# PLC_Relay.net
KiCad netlist of a schematic drawn in Altium Designer
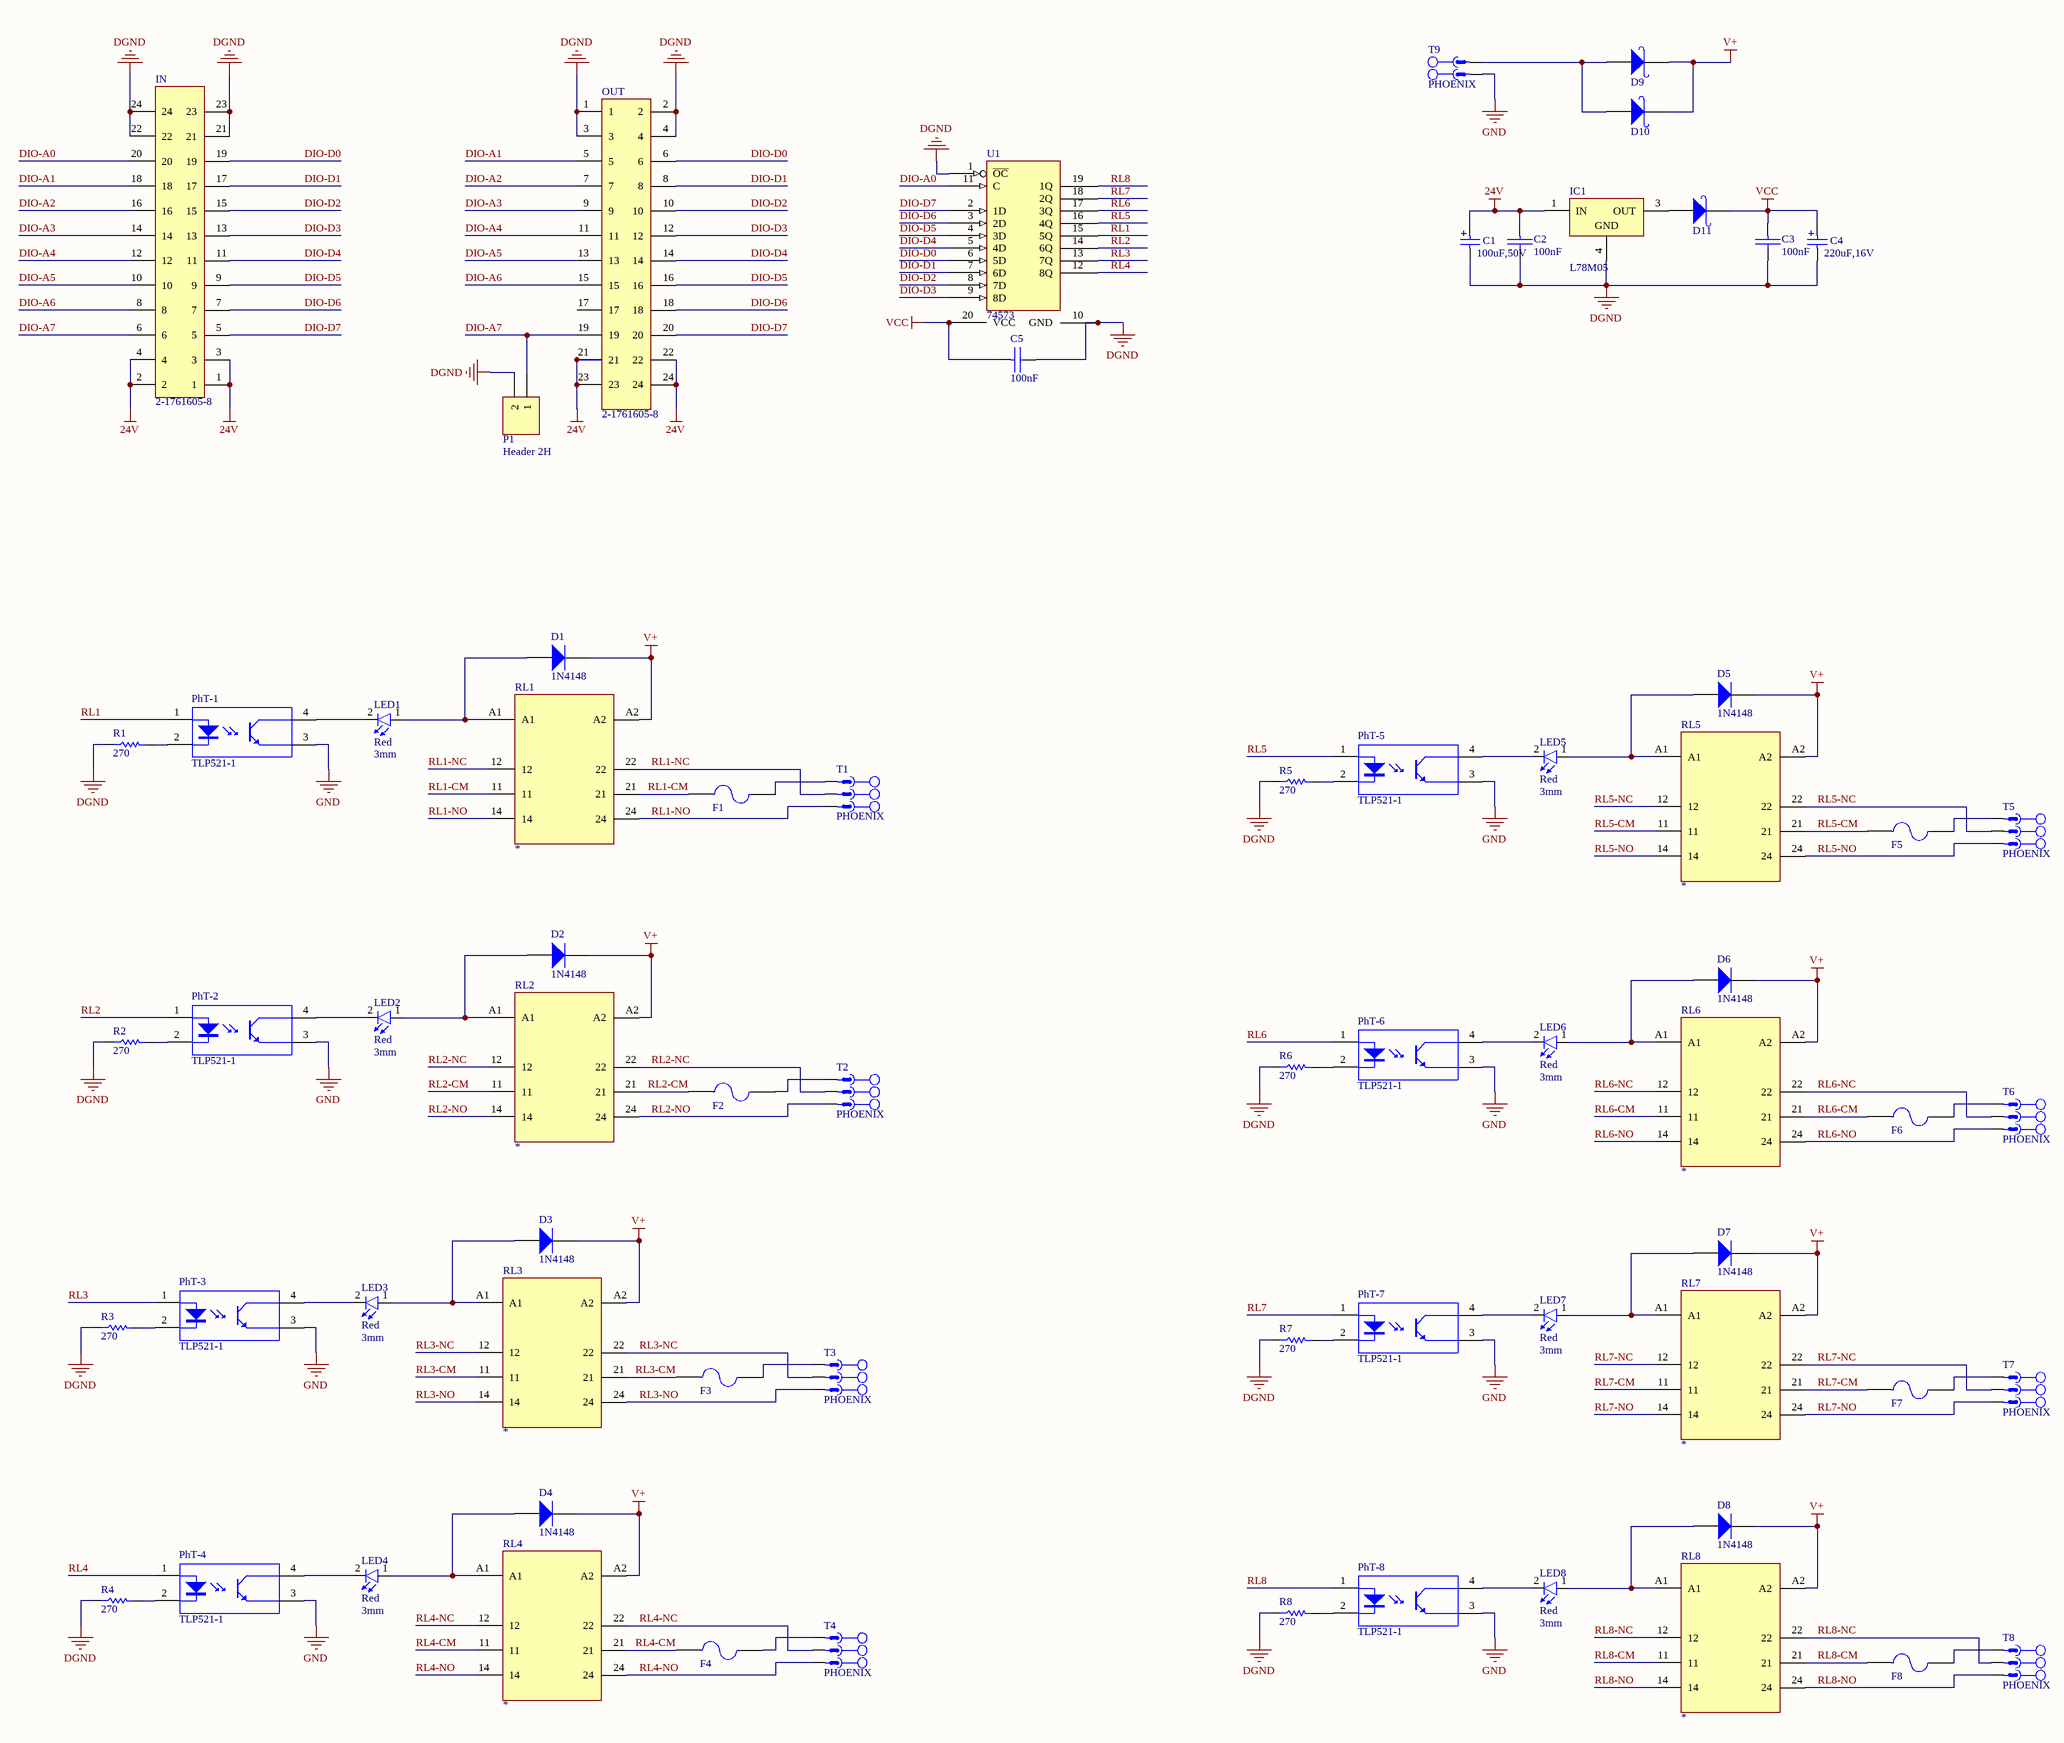
[diagram p0: PLC_Relay.SchDoc]

(export (version "E")
  (design (tool "Eeschema 10.0.6"))
  (components
    (comp (ref "C1")
      (value "100uF,50V")
      (footprint "WCAP-AS5H_8x10.5")
      (description "WCAP-AS5H SMT Aluminum Electrolytic Capacitors, D8mm x L10.5mm, 47uF, +/-20%, 50VDC")
      (fields (field (name "PART NUMBER") "865230653012") (field (name "PUBLISHER") "Wurth Elektronik"))
      (libsource (lib "Altium_WCAP-AS5H (rev19a)") (part "865230653012"))
    )
    (comp (ref "C2")
      (value "100nF")
      (footprint "SMD_CAP_0805")
      (description "Bipolar Capacitor")
      (fields (field (name "VOLTAGE") "100V") (field (name "DESIGNER") "Saeid Jorablo"))
      (libsource (lib "My_Library") (part "Cap-Bipolar"))
    )
    (comp (ref "C3")
      (value "100nF")
      (footprint "SMD_CAP_0805")
      (description "Bipolar Capacitor")
      (fields (field (name "VOLTAGE") "100V") (field (name "DESIGNER") "Saeid Jorablo"))
      (libsource (lib "My_Library") (part "Cap-Bipolar"))
    )
    (comp (ref "C4")
      (value "220uF,16V")
      (footprint "WCAP-AS5H_6.3x7.7")
      (description "WCAP-AS5H SMT Aluminum Electrolytic Capacitors, D6.3mm x L7.7mm, 100uF, +/-20%, 16VDC")
      (fields (field (name "PART NUMBER") "865230345005") (field (name "PUBLISHER") "Wurth Elektronik"))
      (libsource (lib "Altium_WCAP-AS5H (rev19a)") (part "865230345005"))
    )
    (comp (ref "C5")
      (value "100nF")
      (footprint "SMD_CAP_0805")
      (description "Bipolar Capacitor")
      (fields (field (name "VOLTAGE") "100V") (field (name "DESIGNER") "Saeid Jorablo"))
      (libsource (lib "My_Library") (part "Cap-Bipolar"))
    )
    (comp (ref "D1")
      (value "1N4148")
      (footprint "LL4148")
      (description "High Conductance Fast Diode")
      (fields (field (name "PUBLISHER") "Altium Limited"))
      (libsource (lib "My_Library") (part "Diode 1N4148"))
    )
    (comp (ref "D2")
      (value "1N4148")
      (footprint "LL4148")
      (description "High Conductance Fast Diode")
      (fields (field (name "PUBLISHER") "Altium Limited"))
      (libsource (lib "My_Library") (part "Diode 1N4148"))
    )
    (comp (ref "D3")
      (value "1N4148")
      (footprint "LL4148")
      (description "High Conductance Fast Diode")
      (fields (field (name "PUBLISHER") "Altium Limited"))
      (libsource (lib "My_Library") (part "Diode 1N4148"))
    )
    (comp (ref "D4")
      (value "1N4148")
      (footprint "LL4148")
      (description "High Conductance Fast Diode")
      (fields (field (name "PUBLISHER") "Altium Limited"))
      (libsource (lib "My_Library") (part "Diode 1N4148"))
    )
    (comp (ref "D5")
      (value "1N4148")
      (footprint "LL4148")
      (description "High Conductance Fast Diode")
      (fields (field (name "PUBLISHER") "Altium Limited"))
      (libsource (lib "My_Library") (part "Diode 1N4148"))
    )
    (comp (ref "D6")
      (value "1N4148")
      (footprint "LL4148")
      (description "High Conductance Fast Diode")
      (fields (field (name "PUBLISHER") "Altium Limited"))
      (libsource (lib "My_Library") (part "Diode 1N4148"))
    )
    (comp (ref "D7")
      (value "1N4148")
      (footprint "LL4148")
      (description "High Conductance Fast Diode")
      (fields (field (name "PUBLISHER") "Altium Limited"))
      (libsource (lib "My_Library") (part "Diode 1N4148"))
    )
    (comp (ref "D8")
      (value "1N4148")
      (footprint "LL4148")
      (description "High Conductance Fast Diode")
      (fields (field (name "PUBLISHER") "Altium Limited"))
      (libsource (lib "My_Library") (part "Diode 1N4148"))
    )
    (comp (ref "D9")
      (value "1n5822")
      (footprint "Diode 1N4007 SMD")
      (description "Schottky Rectifiers")
      (fields
        (field (name "MANUFACTURER") "ON Semiconductor/Fairchild")
        (field (name "DESIGNER") "Abbas Basereh")
      )
      (libsource (lib "Altium") (part "1N5822 SMD"))
    )
    (comp (ref "D10")
      (value "1n5822")
      (footprint "Diode 1N4007 SMD")
      (description "Schottky Rectifiers")
      (fields
        (field (name "MANUFACTURER") "ON Semiconductor/Fairchild")
        (field (name "DESIGNER") "Abbas Basereh")
      )
      (libsource (lib "Altium") (part "1N5822 SMD"))
    )
    (comp (ref "D11")
      (value "1n5822")
      (footprint "Diode 1N4007 SMD")
      (description "Schottky Rectifiers")
      (fields
        (field (name "MANUFACTURER") "ON Semiconductor/Fairchild")
        (field (name "DESIGNER") "Abbas Basereh")
      )
      (libsource (lib "Altium") (part "1N5822 SMD"))
    )
    (comp (ref "F1")
      (value "F=1.0 A")
      (footprint "Fuse_5x20")
      (description "Fuses 5x20")
      (fields (field (name "DESIGNER") "Abbas Basereh"))
      (libsource (lib "Altium") (part "Fuse 5x20 with holdeer pins"))
    )
    (comp (ref "F2")
      (value "F=1.0 A")
      (footprint "Fuse_5x20")
      (description "Fuses 5x20")
      (fields (field (name "DESIGNER") "Abbas Basereh"))
      (libsource (lib "Altium") (part "Fuse 5x20 with holdeer pins"))
    )
    (comp (ref "F3")
      (value "F=1.0 A")
      (footprint "Fuse_5x20")
      (description "Fuses 5x20")
      (fields (field (name "DESIGNER") "Abbas Basereh"))
      (libsource (lib "Altium") (part "Fuse 5x20 with holdeer pins"))
    )
    (comp (ref "F4")
      (value "F=1.0 A")
      (footprint "Fuse_5x20")
      (description "Fuses 5x20")
      (fields (field (name "DESIGNER") "Abbas Basereh"))
      (libsource (lib "Altium") (part "Fuse 5x20 with holdeer pins"))
    )
    (comp (ref "F5")
      (value "F=1.0 A")
      (footprint "Fuse_5x20")
      (description "Fuses 5x20")
      (fields (field (name "DESIGNER") "Abbas Basereh"))
      (libsource (lib "Altium") (part "Fuse 5x20 with holdeer pins"))
    )
    (comp (ref "F6")
      (value "F=1.0 A")
      (footprint "Fuse_5x20")
      (description "Fuses 5x20")
      (fields (field (name "DESIGNER") "Abbas Basereh"))
      (libsource (lib "Altium") (part "Fuse 5x20 with holdeer pins"))
    )
    (comp (ref "F7")
      (value "F=1.0 A")
      (footprint "Fuse_5x20")
      (description "Fuses 5x20")
      (fields (field (name "DESIGNER") "Abbas Basereh"))
      (libsource (lib "Altium") (part "Fuse 5x20 with holdeer pins"))
    )
    (comp (ref "F8")
      (value "F=1.0 A")
      (footprint "Fuse_5x20")
      (description "Fuses 5x20")
      (fields (field (name "DESIGNER") "Abbas Basereh"))
      (libsource (lib "Altium") (part "Fuse 5x20 with holdeer pins"))
    )
    (comp (ref "IC1")
      (value "L78M05")
      (footprint "TO-252")
      (description "Precision 500mA Regulator")
      (libsource (lib "My_Library") (part "L78M05"))
    )
    (comp (ref "IN")
      (value "2-1761605-8")
      (footprint "TE_2-1761605-8")
      (description "IDC LOW PRO HDR 64P RA BLUE")
      (libsource (lib "") (part "2-1761605-8_1"))
    )
    (comp (ref "LED1")
      (value "Red")
      (footprint "LED-3mm")
      (description "LED")
      (fields
        (field (name "COLOR") "Red")
        (field (name "SIZE") "3mm")
        (field (name "DESIGNER") "Saeid Jorablo")
      )
      (libsource (lib "My_Library") (part "LED"))
    )
    (comp (ref "LED2")
      (value "Red")
      (footprint "LED-3mm")
      (description "LED")
      (fields
        (field (name "COLOR") "Red")
        (field (name "SIZE") "3mm")
        (field (name "DESIGNER") "Saeid Jorablo")
      )
      (libsource (lib "My_Library") (part "LED"))
    )
    (comp (ref "LED3")
      (value "Red")
      (footprint "LED-3mm")
      (description "LED")
      (fields
        (field (name "COLOR") "Red")
        (field (name "SIZE") "3mm")
        (field (name "DESIGNER") "Saeid Jorablo")
      )
      (libsource (lib "My_Library") (part "LED"))
    )
    (comp (ref "LED4")
      (value "Red")
      (footprint "LED-3mm")
      (description "LED")
      (fields
        (field (name "COLOR") "Red")
        (field (name "SIZE") "3mm")
        (field (name "DESIGNER") "Saeid Jorablo")
      )
      (libsource (lib "My_Library") (part "LED"))
    )
    (comp (ref "LED5")
      (value "Red")
      (footprint "LED-3mm")
      (description "LED")
      (fields
        (field (name "COLOR") "Red")
        (field (name "SIZE") "3mm")
        (field (name "DESIGNER") "Saeid Jorablo")
      )
      (libsource (lib "My_Library") (part "LED"))
    )
    (comp (ref "LED6")
      (value "Red")
      (footprint "LED-3mm")
      (description "LED")
      (fields
        (field (name "COLOR") "Red")
        (field (name "SIZE") "3mm")
        (field (name "DESIGNER") "Saeid Jorablo")
      )
      (libsource (lib "My_Library") (part "LED"))
    )
    (comp (ref "LED7")
      (value "Red")
      (footprint "LED-3mm")
      (description "LED")
      (fields
        (field (name "COLOR") "Red")
        (field (name "SIZE") "3mm")
        (field (name "DESIGNER") "Saeid Jorablo")
      )
      (libsource (lib "My_Library") (part "LED"))
    )
    (comp (ref "LED8")
      (value "Red")
      (footprint "LED-3mm")
      (description "LED")
      (fields
        (field (name "COLOR") "Red")
        (field (name "SIZE") "3mm")
        (field (name "DESIGNER") "Saeid Jorablo")
      )
      (libsource (lib "My_Library") (part "LED"))
    )
    (comp (ref "OUT")
      (value "2-1761605-8")
      (footprint "TE_2-1761605-8")
      (description "IDC LOW PRO HDR 64P RA BLUE")
      (libsource (lib "2-1761605-8") (part "2-1761605-8"))
    )
    (comp (ref "P1")
      (value "Header 2H")
      (footprint "HDR1X2H")
      (description "Header, 2-Pin, Right Angle")
      (fields (field (name "PUBLISHER") "Altium Limited"))
      (libsource (lib "Miscellaneous Connectors") (part "Header 2H"))
    )
    (comp (ref "PhT-1")
      (value "TLP521-1")
      (footprint "PCBComponent_1")
      (libsource (lib "TLP521-1") (part "TLP521-1"))
    )
    (comp (ref "PhT-2")
      (value "TLP521-1")
      (footprint "PCBComponent_1")
      (libsource (lib "TLP521-1") (part "TLP521-1"))
    )
    (comp (ref "PhT-3")
      (value "TLP521-1")
      (footprint "PCBComponent_1")
      (libsource (lib "TLP521-1") (part "TLP521-1"))
    )
    (comp (ref "PhT-4")
      (value "TLP521-1")
      (footprint "PCBComponent_1")
      (libsource (lib "TLP521-1") (part "TLP521-1"))
    )
    (comp (ref "PhT-5")
      (value "TLP521-1")
      (footprint "PCBComponent_1")
      (libsource (lib "TLP521-1") (part "TLP521-1"))
    )
    (comp (ref "PhT-6")
      (value "TLP521-1")
      (footprint "PCBComponent_1")
      (libsource (lib "TLP521-1") (part "TLP521-1"))
    )
    (comp (ref "PhT-7")
      (value "TLP521-1")
      (footprint "PCBComponent_1")
      (libsource (lib "TLP521-1") (part "TLP521-1"))
    )
    (comp (ref "PhT-8")
      (value "TLP521-1")
      (footprint "PCBComponent_1")
      (libsource (lib "TLP521-1") (part "TLP521-1"))
    )
    (comp (ref "R1")
      (value "270")
      (footprint "RES 0805 (2012X06L)")
      (description "Resistor")
      (fields (field (name "TOLERANCE") "5%") (field (name "POWER") "1/8 W"))
      (libsource (lib "My_Library") (part "Resistor"))
    )
    (comp (ref "R2")
      (value "270")
      (footprint "RES 0805 (2012X06L)")
      (description "Resistor")
      (fields (field (name "TOLERANCE") "5%") (field (name "POWER") "1/8 W"))
      (libsource (lib "My_Library") (part "Resistor"))
    )
    (comp (ref "R3")
      (value "270")
      (footprint "RES 0805 (2012X06L)")
      (description "Resistor")
      (fields (field (name "TOLERANCE") "5%") (field (name "POWER") "1/8 W"))
      (libsource (lib "My_Library") (part "Resistor"))
    )
    (comp (ref "R4")
      (value "270")
      (footprint "RES 0805 (2012X06L)")
      (description "Resistor")
      (fields (field (name "TOLERANCE") "5%") (field (name "POWER") "1/8 W"))
      (libsource (lib "My_Library") (part "Resistor"))
    )
    (comp (ref "R5")
      (value "270")
      (footprint "RES 0805 (2012X06L)")
      (description "Resistor")
      (fields (field (name "TOLERANCE") "5%") (field (name "POWER") "1/8 W"))
      (libsource (lib "My_Library") (part "Resistor"))
    )
    (comp (ref "R6")
      (value "270")
      (footprint "RES 0805 (2012X06L)")
      (description "Resistor")
      (fields (field (name "TOLERANCE") "5%") (field (name "POWER") "1/8 W"))
      (libsource (lib "My_Library") (part "Resistor"))
    )
    (comp (ref "R7")
      (value "270")
      (footprint "RES 0805 (2012X06L)")
      (description "Resistor")
      (fields (field (name "TOLERANCE") "5%") (field (name "POWER") "1/8 W"))
      (libsource (lib "My_Library") (part "Resistor"))
    )
    (comp (ref "R8")
      (value "270")
      (footprint "RES 0805 (2012X06L)")
      (description "Resistor")
      (fields (field (name "TOLERANCE") "5%") (field (name "POWER") "1/8 W"))
      (libsource (lib "My_Library") (part "Resistor"))
    )
    (comp (ref "RL1")
      (value "MPJ2-S-124-C")
      (footprint "RELAY_RT424024")
      (description "General Purpose Relay DPDT _2 Form C_ 24VDC Coil Through Hole")
      (fields
        (field (name "MP") "RT424024")
        (field (name "MF") "TE Connectivity")
        (field (name "COMMENT_1") "*")
      )
      (libsource (lib "RT424024") (part "RT424024"))
    )
    (comp (ref "RL2")
      (value "MPJ2-S-124-C")
      (footprint "RELAY_RT424024")
      (description "General Purpose Relay DPDT _2 Form C_ 24VDC Coil Through Hole")
      (fields
        (field (name "MP") "RT424024")
        (field (name "MF") "TE Connectivity")
        (field (name "COMMENT_1") "*")
      )
      (libsource (lib "RT424024") (part "RT424024"))
    )
    (comp (ref "RL3")
      (value "MPJ2-S-124-C")
      (footprint "RELAY_RT424024")
      (description "General Purpose Relay DPDT _2 Form C_ 24VDC Coil Through Hole")
      (fields
        (field (name "MP") "RT424024")
        (field (name "MF") "TE Connectivity")
        (field (name "COMMENT_1") "*")
      )
      (libsource (lib "RT424024") (part "RT424024"))
    )
    (comp (ref "RL4")
      (value "MPJ2-S-124-C")
      (footprint "RELAY_RT424024")
      (description "General Purpose Relay DPDT _2 Form C_ 24VDC Coil Through Hole")
      (fields
        (field (name "MP") "RT424024")
        (field (name "MF") "TE Connectivity")
        (field (name "COMMENT_1") "*")
      )
      (libsource (lib "RT424024") (part "RT424024"))
    )
    (comp (ref "RL5")
      (value "MPJ2-S-124-C")
      (footprint "RELAY_RT424024")
      (description "General Purpose Relay DPDT _2 Form C_ 24VDC Coil Through Hole")
      (fields
        (field (name "MP") "RT424024")
        (field (name "MF") "TE Connectivity")
        (field (name "COMMENT_1") "*")
      )
      (libsource (lib "RT424024") (part "RT424024"))
    )
    (comp (ref "RL6")
      (value "MPJ2-S-124-C")
      (footprint "RELAY_RT424024")
      (description "General Purpose Relay DPDT _2 Form C_ 24VDC Coil Through Hole")
      (fields
        (field (name "MP") "RT424024")
        (field (name "MF") "TE Connectivity")
        (field (name "COMMENT_1") "*")
      )
      (libsource (lib "RT424024") (part "RT424024"))
    )
    (comp (ref "RL7")
      (value "MPJ2-S-124-C")
      (footprint "RELAY_RT424024")
      (description "General Purpose Relay DPDT _2 Form C_ 24VDC Coil Through Hole")
      (fields
        (field (name "MP") "RT424024")
        (field (name "MF") "TE Connectivity")
        (field (name "COMMENT_1") "*")
      )
      (libsource (lib "RT424024") (part "RT424024"))
    )
    (comp (ref "RL8")
      (value "MPJ2-S-124-C")
      (footprint "RELAY_RT424024")
      (description "General Purpose Relay DPDT _2 Form C_ 24VDC Coil Through Hole")
      (fields
        (field (name "MP") "RT424024")
        (field (name "MF") "TE Connectivity")
        (field (name "COMMENT_1") "*")
      )
      (libsource (lib "RT424024") (part "RT424024"))
    )
    (comp (ref "T1")
      (value "PHOENIX")
      (footprint "MSTB 2,5/3-G-5,08")
      (description "3 Pitch: 5.08 mm Color: green Contact surface: Tin Assembly")
      (fields
        (field (name "MANUFACTURER") "PHOENIX CONTACT")
        (field (name "VOLTAGE") "320 V")
        (field (name "DESIGNER") "ABBAS BASEREH")
      )
      (libsource (lib "Altium") (part "CON_Phoenix_MSTB_03"))
    )
    (comp (ref "T2")
      (value "PHOENIX")
      (footprint "MSTB 2,5/3-G-5,08")
      (description "3 Pitch: 5.08 mm Color: green Contact surface: Tin Assembly")
      (fields
        (field (name "MANUFACTURER") "PHOENIX CONTACT")
        (field (name "VOLTAGE") "320 V")
        (field (name "DESIGNER") "ABBAS BASEREH")
      )
      (libsource (lib "Altium") (part "CON_Phoenix_MSTB_03"))
    )
    (comp (ref "T3")
      (value "PHOENIX")
      (footprint "MSTB 2,5/3-G-5,08")
      (description "3 Pitch: 5.08 mm Color: green Contact surface: Tin Assembly")
      (fields
        (field (name "MANUFACTURER") "PHOENIX CONTACT")
        (field (name "VOLTAGE") "320 V")
        (field (name "DESIGNER") "ABBAS BASEREH")
      )
      (libsource (lib "Altium") (part "CON_Phoenix_MSTB_03"))
    )
    (comp (ref "T4")
      (value "PHOENIX")
      (footprint "MSTB 2,5/3-G-5,08")
      (description "3 Pitch: 5.08 mm Color: green Contact surface: Tin Assembly")
      (fields
        (field (name "MANUFACTURER") "PHOENIX CONTACT")
        (field (name "VOLTAGE") "320 V")
        (field (name "DESIGNER") "ABBAS BASEREH")
      )
      (libsource (lib "Altium") (part "CON_Phoenix_MSTB_03"))
    )
    (comp (ref "T5")
      (value "PHOENIX")
      (footprint "MSTB 2,5/3-G-5,08")
      (description "3 Pitch: 5.08 mm Color: green Contact surface: Tin Assembly")
      (fields
        (field (name "MANUFACTURER") "PHOENIX CONTACT")
        (field (name "VOLTAGE") "320 V")
        (field (name "DESIGNER") "ABBAS BASEREH")
      )
      (libsource (lib "Altium") (part "CON_Phoenix_MSTB_03"))
    )
    (comp (ref "T6")
      (value "PHOENIX")
      (footprint "MSTB 2,5/3-G-5,08")
      (description "3 Pitch: 5.08 mm Color: green Contact surface: Tin Assembly")
      (fields
        (field (name "MANUFACTURER") "PHOENIX CONTACT")
        (field (name "VOLTAGE") "320 V")
        (field (name "DESIGNER") "ABBAS BASEREH")
      )
      (libsource (lib "Altium") (part "CON_Phoenix_MSTB_03"))
    )
    (comp (ref "T7")
      (value "PHOENIX")
      (footprint "MSTB 2,5/3-G-5,08")
      (description "3 Pitch: 5.08 mm Color: green Contact surface: Tin Assembly")
      (fields
        (field (name "MANUFACTURER") "PHOENIX CONTACT")
        (field (name "VOLTAGE") "320 V")
        (field (name "DESIGNER") "ABBAS BASEREH")
      )
      (libsource (lib "Altium") (part "CON_Phoenix_MSTB_03"))
    )
    (comp (ref "T8")
      (value "PHOENIX")
      (footprint "MSTB 2,5/3-G-5,08")
      (description "3 Pitch: 5.08 mm Color: green Contact surface: Tin Assembly")
      (fields
        (field (name "MANUFACTURER") "PHOENIX CONTACT")
        (field (name "VOLTAGE") "320 V")
        (field (name "DESIGNER") "ABBAS BASEREH")
      )
      (libsource (lib "Altium") (part "CON_Phoenix_MSTB_03"))
    )
    (comp (ref "T9")
      (value "PHOENIX")
      (footprint "MSTB 2,5/2-G-5,08")
      (description "2 Pitch: 5.08 mm Color: green Contact surface: Tin Assembly")
      (fields
        (field (name "MANUFACTURER") "PHOENIX CONTACT")
        (field (name "VOLTAGE") "320 V")
        (field (name "DESIGNER") "ABBAS BASEREH")
      )
      (libsource (lib "Altium") (part "CON_Phoenix_MSTB_02"))
    )
    (comp (ref "U1")
      (value "74573")
      (footprint "SO20_M")
      (description "OCTAL D-TYPE TRANSPARENT LCH")
      (libsource (lib "Altium library (www.AVRelec.com)") (part "74573"))
    )
  )
  (nets
    (net (code "1") (name "/DIO-A0") (class "Default")
      (node (ref "IN") (pin "20") (pinfunction "20_20") (pintype "passive"))
      (node (ref "U1") (pin "11") (pinfunction "C_11") (pintype "input"))
    )
    (net (code "2") (name "/DIO-A1") (class "Default")
      (node (ref "IN") (pin "18") (pinfunction "18_18") (pintype "passive"))
      (node (ref "OUT") (pin "5") (pinfunction "5_5") (pintype "passive"))
    )
    (net (code "3") (name "/DIO-A2") (class "Default")
      (node (ref "IN") (pin "16") (pinfunction "16_16") (pintype "passive"))
      (node (ref "OUT") (pin "7") (pinfunction "7_7") (pintype "passive"))
    )
    (net (code "4") (name "/DIO-A3") (class "Default")
      (node (ref "IN") (pin "14") (pinfunction "14_14") (pintype "passive"))
      (node (ref "OUT") (pin "9") (pinfunction "9_9") (pintype "passive"))
    )
    (net (code "5") (name "/DIO-A4") (class "Default")
      (node (ref "IN") (pin "12") (pinfunction "12_12") (pintype "passive"))
      (node (ref "OUT") (pin "11") (pinfunction "11_11") (pintype "passive"))
    )
    (net (code "6") (name "/DIO-A5") (class "Default")
      (node (ref "IN") (pin "10") (pinfunction "10_10") (pintype "passive"))
      (node (ref "OUT") (pin "13") (pinfunction "13_13") (pintype "passive"))
    )
    (net (code "7") (name "/DIO-A6") (class "Default")
      (node (ref "IN") (pin "8") (pinfunction "8_8") (pintype "passive"))
      (node (ref "OUT") (pin "15") (pinfunction "15_15") (pintype "passive"))
    )
    (net (code "8") (name "/DIO-A7") (class "Default")
      (node (ref "IN") (pin "6") (pinfunction "6_6") (pintype "passive"))
      (node (ref "OUT") (pin "19") (pinfunction "19_19") (pintype "passive"))
      (node (ref "P1") (pin "1") (pinfunction "1_1") (pintype "passive"))
    )
    (net (code "9") (name "/DIO-D0") (class "Default")
      (node (ref "IN") (pin "19") (pinfunction "19_19") (pintype "passive"))
      (node (ref "OUT") (pin "6") (pinfunction "6_6") (pintype "passive"))
      (node (ref "U1") (pin "6") (pinfunction "5D_6") (pintype "input"))
    )
    (net (code "10") (name "/DIO-D1") (class "Default")
      (node (ref "IN") (pin "17") (pinfunction "17_17") (pintype "passive"))
      (node (ref "OUT") (pin "8") (pinfunction "8_8") (pintype "passive"))
      (node (ref "U1") (pin "7") (pinfunction "6D_7") (pintype "input"))
    )
    (net (code "11") (name "/DIO-D2") (class "Default")
      (node (ref "IN") (pin "15") (pinfunction "15_15") (pintype "passive"))
      (node (ref "OUT") (pin "10") (pinfunction "10_10") (pintype "passive"))
      (node (ref "U1") (pin "8") (pinfunction "7D_8") (pintype "input"))
    )
    (net (code "12") (name "/DIO-D3") (class "Default")
      (node (ref "IN") (pin "13") (pinfunction "13_13") (pintype "passive"))
      (node (ref "OUT") (pin "12") (pinfunction "12_12") (pintype "passive"))
      (node (ref "U1") (pin "9") (pinfunction "8D_9") (pintype "input"))
    )
    (net (code "13") (name "/DIO-D4") (class "Default")
      (node (ref "IN") (pin "11") (pinfunction "11_11") (pintype "passive"))
      (node (ref "OUT") (pin "14") (pinfunction "14_14") (pintype "passive"))
      (node (ref "U1") (pin "5") (pinfunction "4D_5") (pintype "input"))
    )
    (net (code "14") (name "/DIO-D5") (class "Default")
      (node (ref "IN") (pin "9") (pinfunction "9_9") (pintype "passive"))
      (node (ref "OUT") (pin "16") (pinfunction "16_16") (pintype "passive"))
      (node (ref "U1") (pin "4") (pinfunction "3D_4") (pintype "input"))
    )
    (net (code "15") (name "/DIO-D6") (class "Default")
      (node (ref "IN") (pin "7") (pinfunction "7_7") (pintype "passive"))
      (node (ref "OUT") (pin "18") (pinfunction "18_18") (pintype "passive"))
      (node (ref "U1") (pin "3") (pinfunction "2D_3") (pintype "input"))
    )
    (net (code "16") (name "/DIO-D7") (class "Default")
      (node (ref "IN") (pin "5") (pinfunction "5_5") (pintype "passive"))
      (node (ref "OUT") (pin "20") (pinfunction "20_20") (pintype "passive"))
      (node (ref "U1") (pin "2") (pinfunction "1D_2") (pintype "input"))
    )
    (net (code "17") (name "/RL1") (class "Default")
      (node (ref "PhT-1") (pin "1") (pinfunction "A_1") (pintype "passive"))
      (node (ref "U1") (pin "15") (pinfunction "5Q_15") (pintype "tri_state"))
    )
    (net (code "18") (name "/RL1-CM") (class "Default")
      (node (ref "F1") (pin "1") (pinfunction "1_1") (pintype "passive"))
      (node (ref "RL1") (pin "11") (pinfunction "11_11") (pintype "passive"))
      (node (ref "RL1") (pin "21") (pinfunction "21_21") (pintype "passive"))
    )
    (net (code "19") (name "/RL1-NC") (class "Default")
      (node (ref "RL1") (pin "12") (pinfunction "12_12") (pintype "passive"))
      (node (ref "RL1") (pin "22") (pinfunction "22_22") (pintype "passive"))
      (node (ref "T1") (pin "2") (pinfunction "2_2") (pintype "passive"))
    )
    (net (code "20") (name "/RL1-NO") (class "Default")
      (node (ref "RL1") (pin "14") (pinfunction "14_14") (pintype "passive"))
      (node (ref "RL1") (pin "24") (pinfunction "24_24") (pintype "passive"))
      (node (ref "T1") (pin "3") (pinfunction "3_3") (pintype "passive"))
    )
    (net (code "21") (name "/RL2") (class "Default")
      (node (ref "PhT-2") (pin "1") (pinfunction "A_1") (pintype "passive"))
      (node (ref "U1") (pin "14") (pinfunction "6Q_14") (pintype "tri_state"))
    )
    (net (code "22") (name "/RL2-CM") (class "Default")
      (node (ref "F2") (pin "1") (pinfunction "1_1") (pintype "passive"))
      (node (ref "RL2") (pin "11") (pinfunction "11_11") (pintype "passive"))
      (node (ref "RL2") (pin "21") (pinfunction "21_21") (pintype "passive"))
    )
    (net (code "23") (name "/RL2-NC") (class "Default")
      (node (ref "RL2") (pin "12") (pinfunction "12_12") (pintype "passive"))
      (node (ref "RL2") (pin "22") (pinfunction "22_22") (pintype "passive"))
      (node (ref "T2") (pin "2") (pinfunction "2_2") (pintype "passive"))
    )
    (net (code "24") (name "/RL2-NO") (class "Default")
      (node (ref "RL2") (pin "14") (pinfunction "14_14") (pintype "passive"))
      (node (ref "RL2") (pin "24") (pinfunction "24_24") (pintype "passive"))
      (node (ref "T2") (pin "3") (pinfunction "3_3") (pintype "passive"))
    )
    (net (code "25") (name "/RL3") (class "Default")
      (node (ref "PhT-3") (pin "1") (pinfunction "A_1") (pintype "passive"))
      (node (ref "U1") (pin "13") (pinfunction "7Q_13") (pintype "tri_state"))
    )
    (net (code "26") (name "/RL3-CM") (class "Default")
      (node (ref "F3") (pin "1") (pinfunction "1_1") (pintype "passive"))
      (node (ref "RL3") (pin "11") (pinfunction "11_11") (pintype "passive"))
      (node (ref "RL3") (pin "21") (pinfunction "21_21") (pintype "passive"))
    )
    (net (code "27") (name "/RL3-NC") (class "Default")
      (node (ref "RL3") (pin "12") (pinfunction "12_12") (pintype "passive"))
      (node (ref "RL3") (pin "22") (pinfunction "22_22") (pintype "passive"))
      (node (ref "T3") (pin "2") (pinfunction "2_2") (pintype "passive"))
    )
    (net (code "28") (name "/RL3-NO") (class "Default")
      (node (ref "RL3") (pin "14") (pinfunction "14_14") (pintype "passive"))
      (node (ref "RL3") (pin "24") (pinfunction "24_24") (pintype "passive"))
      (node (ref "T3") (pin "3") (pinfunction "3_3") (pintype "passive"))
    )
    (net (code "29") (name "/RL4") (class "Default")
      (node (ref "PhT-4") (pin "1") (pinfunction "A_1") (pintype "passive"))
      (node (ref "U1") (pin "12") (pinfunction "8Q_12") (pintype "tri_state"))
    )
    (net (code "30") (name "/RL4-CM") (class "Default")
      (node (ref "F4") (pin "1") (pinfunction "1_1") (pintype "passive"))
      (node (ref "RL4") (pin "11") (pinfunction "11_11") (pintype "passive"))
      (node (ref "RL4") (pin "21") (pinfunction "21_21") (pintype "passive"))
    )
    (net (code "31") (name "/RL4-NC") (class "Default")
      (node (ref "RL4") (pin "12") (pinfunction "12_12") (pintype "passive"))
      (node (ref "RL4") (pin "22") (pinfunction "22_22") (pintype "passive"))
      (node (ref "T4") (pin "2") (pinfunction "2_2") (pintype "passive"))
    )
    (net (code "32") (name "/RL4-NO") (class "Default")
      (node (ref "RL4") (pin "14") (pinfunction "14_14") (pintype "passive"))
      (node (ref "RL4") (pin "24") (pinfunction "24_24") (pintype "passive"))
      (node (ref "T4") (pin "3") (pinfunction "3_3") (pintype "passive"))
    )
    (net (code "33") (name "/RL5") (class "Default")
      (node (ref "PhT-5") (pin "1") (pinfunction "A_1") (pintype "passive"))
      (node (ref "U1") (pin "16") (pinfunction "4Q_16") (pintype "tri_state"))
    )
    (net (code "34") (name "/RL5-CM") (class "Default")
      (node (ref "F5") (pin "1") (pinfunction "1_1") (pintype "passive"))
      (node (ref "RL5") (pin "11") (pinfunction "11_11") (pintype "passive"))
      (node (ref "RL5") (pin "21") (pinfunction "21_21") (pintype "passive"))
    )
    (net (code "35") (name "/RL5-NC") (class "Default")
      (node (ref "RL5") (pin "12") (pinfunction "12_12") (pintype "passive"))
      (node (ref "RL5") (pin "22") (pinfunction "22_22") (pintype "passive"))
      (node (ref "T5") (pin "2") (pinfunction "2_2") (pintype "passive"))
    )
    (net (code "36") (name "/RL5-NO") (class "Default")
      (node (ref "RL5") (pin "14") (pinfunction "14_14") (pintype "passive"))
      (node (ref "RL5") (pin "24") (pinfunction "24_24") (pintype "passive"))
      (node (ref "T5") (pin "3") (pinfunction "3_3") (pintype "passive"))
    )
    (net (code "37") (name "/RL6") (class "Default")
      (node (ref "PhT-6") (pin "1") (pinfunction "A_1") (pintype "passive"))
      (node (ref "U1") (pin "17") (pinfunction "3Q_17") (pintype "tri_state"))
    )
    (net (code "38") (name "/RL6-CM") (class "Default")
      (node (ref "F6") (pin "1") (pinfunction "1_1") (pintype "passive"))
      (node (ref "RL6") (pin "11") (pinfunction "11_11") (pintype "passive"))
      (node (ref "RL6") (pin "21") (pinfunction "21_21") (pintype "passive"))
    )
    (net (code "39") (name "/RL6-NC") (class "Default")
      (node (ref "RL6") (pin "12") (pinfunction "12_12") (pintype "passive"))
      (node (ref "RL6") (pin "22") (pinfunction "22_22") (pintype "passive"))
      (node (ref "T6") (pin "2") (pinfunction "2_2") (pintype "passive"))
    )
    (net (code "40") (name "/RL6-NO") (class "Default")
      (node (ref "RL6") (pin "14") (pinfunction "14_14") (pintype "passive"))
      (node (ref "RL6") (pin "24") (pinfunction "24_24") (pintype "passive"))
      (node (ref "T6") (pin "3") (pinfunction "3_3") (pintype "passive"))
    )
    (net (code "41") (name "/RL7") (class "Default")
      (node (ref "PhT-7") (pin "1") (pinfunction "A_1") (pintype "passive"))
      (node (ref "U1") (pin "18") (pinfunction "2Q_18") (pintype "tri_state"))
    )
    (net (code "42") (name "/RL7-CM") (class "Default")
      (node (ref "F7") (pin "1") (pinfunction "1_1") (pintype "passive"))
      (node (ref "RL7") (pin "11") (pinfunction "11_11") (pintype "passive"))
      (node (ref "RL7") (pin "21") (pinfunction "21_21") (pintype "passive"))
    )
    (net (code "43") (name "/RL7-NC") (class "Default")
      (node (ref "RL7") (pin "12") (pinfunction "12_12") (pintype "passive"))
      (node (ref "RL7") (pin "22") (pinfunction "22_22") (pintype "passive"))
      (node (ref "T7") (pin "2") (pinfunction "2_2") (pintype "passive"))
    )
    (net (code "44") (name "/RL7-NO") (class "Default")
      (node (ref "RL7") (pin "14") (pinfunction "14_14") (pintype "passive"))
      (node (ref "RL7") (pin "24") (pinfunction "24_24") (pintype "passive"))
      (node (ref "T7") (pin "3") (pinfunction "3_3") (pintype "passive"))
    )
    (net (code "45") (name "/RL8") (class "Default")
      (node (ref "PhT-8") (pin "1") (pinfunction "A_1") (pintype "passive"))
      (node (ref "U1") (pin "19") (pinfunction "1Q_19") (pintype "tri_state"))
    )
    (net (code "46") (name "/RL8-CM") (class "Default")
      (node (ref "F8") (pin "1") (pinfunction "1_1") (pintype "passive"))
      (node (ref "RL8") (pin "11") (pinfunction "11_11") (pintype "passive"))
      (node (ref "RL8") (pin "21") (pinfunction "21_21") (pintype "passive"))
    )
    (net (code "47") (name "/RL8-NC") (class "Default")
      (node (ref "RL8") (pin "12") (pinfunction "12_12") (pintype "passive"))
      (node (ref "RL8") (pin "22") (pinfunction "22_22") (pintype "passive"))
      (node (ref "T8") (pin "2") (pinfunction "2_2") (pintype "passive"))
    )
    (net (code "48") (name "/RL8-NO") (class "Default")
      (node (ref "RL8") (pin "14") (pinfunction "14_14") (pintype "passive"))
      (node (ref "RL8") (pin "24") (pinfunction "24_24") (pintype "passive"))
      (node (ref "T8") (pin "3") (pinfunction "3_3") (pintype "passive"))
    )
    (net (code "49") (name "24V") (class "Default")
      (node (ref "C1") (pin "2") (pinfunction "P_2") (pintype "passive"))
      (node (ref "C2") (pin "2") (pinfunction "-_2") (pintype "passive"))
      (node (ref "IC1") (pin "1") (pinfunction "IN_1") (pintype "power_in"))
      (node (ref "IN") (pin "1") (pinfunction "1_1") (pintype "passive"))
      (node (ref "IN") (pin "2") (pinfunction "2_2") (pintype "passive"))
      (node (ref "IN") (pin "3") (pinfunction "3_3") (pintype "passive"))
      (node (ref "IN") (pin "4") (pinfunction "4_4") (pintype "passive"))
      (node (ref "OUT") (pin "21") (pinfunction "21_21") (pintype "passive"))
      (node (ref "OUT") (pin "22") (pinfunction "22_22") (pintype "passive"))
      (node (ref "OUT") (pin "23") (pinfunction "23_23") (pintype "passive"))
      (node (ref "OUT") (pin "24") (pinfunction "24_24") (pintype "passive"))
    )
    (net (code "50") (name "DGND") (class "Default")
      (node (ref "C1") (pin "1") (pinfunction "N_1") (pintype "passive"))
      (node (ref "C2") (pin "1") (pinfunction "+_1") (pintype "passive"))
      (node (ref "C3") (pin "1") (pinfunction "+_1") (pintype "passive"))
      (node (ref "C4") (pin "1") (pinfunction "N_1") (pintype "passive"))
      (node (ref "C5") (pin "1") (pinfunction "+_1") (pintype "passive"))
      (node (ref "IC1") (pin "4") (pinfunction "GND_4") (pintype "power_in"))
      (node (ref "IN") (pin "21") (pinfunction "21_21") (pintype "passive"))
      (node (ref "IN") (pin "22") (pinfunction "22_22") (pintype "passive"))
      (node (ref "IN") (pin "23") (pinfunction "23_23") (pintype "passive"))
      (node (ref "IN") (pin "24") (pinfunction "24_24") (pintype "passive"))
      (node (ref "OUT") (pin "1") (pinfunction "1_1") (pintype "passive"))
      (node (ref "OUT") (pin "2") (pinfunction "2_2") (pintype "passive"))
      (node (ref "OUT") (pin "3") (pinfunction "3_3") (pintype "passive"))
      (node (ref "OUT") (pin "4") (pinfunction "4_4") (pintype "passive"))
      (node (ref "P1") (pin "2") (pinfunction "2_2") (pintype "passive"))
      (node (ref "PhT-1") (pin "3") (pinfunction "E_3") (pintype "passive"))
      (node (ref "PhT-2") (pin "3") (pinfunction "E_3") (pintype "passive"))
      (node (ref "PhT-3") (pin "3") (pinfunction "E_3") (pintype "passive"))
      (node (ref "PhT-4") (pin "3") (pinfunction "E_3") (pintype "passive"))
      (node (ref "PhT-5") (pin "3") (pinfunction "E_3") (pintype "passive"))
      (node (ref "PhT-6") (pin "3") (pinfunction "E_3") (pintype "passive"))
      (node (ref "PhT-7") (pin "3") (pinfunction "E_3") (pintype "passive"))
      (node (ref "PhT-8") (pin "3") (pinfunction "E_3") (pintype "passive"))
      (node (ref "R1") (pin "1") (pinfunction "1_1") (pintype "passive"))
      (node (ref "R2") (pin "1") (pinfunction "1_1") (pintype "passive"))
      (node (ref "R3") (pin "1") (pinfunction "1_1") (pintype "passive"))
      (node (ref "R4") (pin "1") (pinfunction "1_1") (pintype "passive"))
      (node (ref "R5") (pin "1") (pinfunction "1_1") (pintype "passive"))
      (node (ref "R6") (pin "1") (pinfunction "1_1") (pintype "passive"))
      (node (ref "R7") (pin "1") (pinfunction "1_1") (pintype "passive"))
      (node (ref "R8") (pin "1") (pinfunction "1_1") (pintype "passive"))
      (node (ref "T9") (pin "1") (pinfunction "1_1") (pintype "passive"))
      (node (ref "U1") (pin "1") (pinfunction "~{OC}_1") (pintype "input"))
      (node (ref "U1") (pin "10") (pinfunction "GND_10") (pintype "power_in"))
    )
    (net (code "51") (name "Net-(D1-A)") (class "Default")
      (node (ref "D1") (pin "1") (pinfunction "A_1") (pintype "passive"))
      (node (ref "LED1") (pin "1") (pinfunction "A_1") (pintype "passive"))
      (node (ref "RL1") (pin "A1") (pinfunction "A1_A1") (pintype "passive"))
    )
    (net (code "52") (name "Net-(D2-A)") (class "Default")
      (node (ref "D2") (pin "1") (pinfunction "A_1") (pintype "passive"))
      (node (ref "LED2") (pin "1") (pinfunction "A_1") (pintype "passive"))
      (node (ref "RL2") (pin "A1") (pinfunction "A1_A1") (pintype "passive"))
    )
    (net (code "53") (name "Net-(D3-A)") (class "Default")
      (node (ref "D3") (pin "1") (pinfunction "A_1") (pintype "passive"))
      (node (ref "LED3") (pin "1") (pinfunction "A_1") (pintype "passive"))
      (node (ref "RL3") (pin "A1") (pinfunction "A1_A1") (pintype "passive"))
    )
    (net (code "54") (name "Net-(D4-A)") (class "Default")
      (node (ref "D4") (pin "1") (pinfunction "A_1") (pintype "passive"))
      (node (ref "LED4") (pin "1") (pinfunction "A_1") (pintype "passive"))
      (node (ref "RL4") (pin "A1") (pinfunction "A1_A1") (pintype "passive"))
    )
    (net (code "55") (name "Net-(D5-A)") (class "Default")
      (node (ref "D5") (pin "1") (pinfunction "A_1") (pintype "passive"))
      (node (ref "LED5") (pin "1") (pinfunction "A_1") (pintype "passive"))
      (node (ref "RL5") (pin "A1") (pinfunction "A1_A1") (pintype "passive"))
    )
    (net (code "56") (name "Net-(D6-A)") (class "Default")
      (node (ref "D6") (pin "1") (pinfunction "A_1") (pintype "passive"))
      (node (ref "LED6") (pin "1") (pinfunction "A_1") (pintype "passive"))
      (node (ref "RL6") (pin "A1") (pinfunction "A1_A1") (pintype "passive"))
    )
    (net (code "57") (name "Net-(D7-A)") (class "Default")
      (node (ref "D7") (pin "1") (pinfunction "A_1") (pintype "passive"))
      (node (ref "LED7") (pin "1") (pinfunction "A_1") (pintype "passive"))
      (node (ref "RL7") (pin "A1") (pinfunction "A1_A1") (pintype "passive"))
    )
    (net (code "58") (name "Net-(D8-A)") (class "Default")
      (node (ref "D8") (pin "1") (pinfunction "A_1") (pintype "passive"))
      (node (ref "LED8") (pin "1") (pinfunction "A_1") (pintype "passive"))
      (node (ref "RL8") (pin "A1") (pinfunction "A1_A1") (pintype "passive"))
    )
    (net (code "59") (name "Net-(D10-A)") (class "Default")
      (node (ref "D10") (pin "1") (pinfunction "A_1") (pintype "passive"))
      (node (ref "D9") (pin "1") (pinfunction "A_1") (pintype "passive"))
      (node (ref "T9") (pin "2") (pinfunction "2_2") (pintype "passive"))
    )
    (net (code "60") (name "Net-(D11-A)") (class "Default")
      (node (ref "D11") (pin "1") (pinfunction "A_1") (pintype "passive"))
      (node (ref "IC1") (pin "3") (pinfunction "OUT_3") (pintype "power_in"))
    )
    (net (code "61") (name "Net-(F1-Pad2)") (class "Default")
      (node (ref "F1") (pin "2") (pinfunction "2_2") (pintype "passive"))
      (node (ref "T1") (pin "1") (pinfunction "1_1") (pintype "passive"))
    )
    (net (code "62") (name "Net-(F2-Pad2)") (class "Default")
      (node (ref "F2") (pin "2") (pinfunction "2_2") (pintype "passive"))
      (node (ref "T2") (pin "1") (pinfunction "1_1") (pintype "passive"))
    )
    (net (code "63") (name "Net-(F3-Pad2)") (class "Default")
      (node (ref "F3") (pin "2") (pinfunction "2_2") (pintype "passive"))
      (node (ref "T3") (pin "1") (pinfunction "1_1") (pintype "passive"))
    )
    (net (code "64") (name "Net-(F4-Pad2)") (class "Default")
      (node (ref "F4") (pin "2") (pinfunction "2_2") (pintype "passive"))
      (node (ref "T4") (pin "1") (pinfunction "1_1") (pintype "passive"))
    )
    (net (code "65") (name "Net-(F5-Pad2)") (class "Default")
      (node (ref "F5") (pin "2") (pinfunction "2_2") (pintype "passive"))
      (node (ref "T5") (pin "1") (pinfunction "1_1") (pintype "passive"))
    )
    (net (code "66") (name "Net-(F6-Pad2)") (class "Default")
      (node (ref "F6") (pin "2") (pinfunction "2_2") (pintype "passive"))
      (node (ref "T6") (pin "1") (pinfunction "1_1") (pintype "passive"))
    )
    (net (code "67") (name "Net-(F7-Pad2)") (class "Default")
      (node (ref "F7") (pin "2") (pinfunction "2_2") (pintype "passive"))
      (node (ref "T7") (pin "1") (pinfunction "1_1") (pintype "passive"))
    )
    (net (code "68") (name "Net-(F8-Pad2)") (class "Default")
      (node (ref "F8") (pin "2") (pinfunction "2_2") (pintype "passive"))
      (node (ref "T8") (pin "1") (pinfunction "1_1") (pintype "passive"))
    )
    (net (code "69") (name "Net-(LED1-K)") (class "Default")
      (node (ref "LED1") (pin "2") (pinfunction "K_2") (pintype "passive"))
      (node (ref "PhT-1") (pin "4") (pinfunction "C_4") (pintype "passive"))
    )
    (net (code "70") (name "Net-(LED2-K)") (class "Default")
      (node (ref "LED2") (pin "2") (pinfunction "K_2") (pintype "passive"))
      (node (ref "PhT-2") (pin "4") (pinfunction "C_4") (pintype "passive"))
    )
    (net (code "71") (name "Net-(LED3-K)") (class "Default")
      (node (ref "LED3") (pin "2") (pinfunction "K_2") (pintype "passive"))
      (node (ref "PhT-3") (pin "4") (pinfunction "C_4") (pintype "passive"))
    )
    (net (code "72") (name "Net-(LED4-K)") (class "Default")
      (node (ref "LED4") (pin "2") (pinfunction "K_2") (pintype "passive"))
      (node (ref "PhT-4") (pin "4") (pinfunction "C_4") (pintype "passive"))
    )
    (net (code "73") (name "Net-(LED5-K)") (class "Default")
      (node (ref "LED5") (pin "2") (pinfunction "K_2") (pintype "passive"))
      (node (ref "PhT-5") (pin "4") (pinfunction "C_4") (pintype "passive"))
    )
    (net (code "74") (name "Net-(LED6-K)") (class "Default")
      (node (ref "LED6") (pin "2") (pinfunction "K_2") (pintype "passive"))
      (node (ref "PhT-6") (pin "4") (pinfunction "C_4") (pintype "passive"))
    )
    (net (code "75") (name "Net-(LED7-K)") (class "Default")
      (node (ref "LED7") (pin "2") (pinfunction "K_2") (pintype "passive"))
      (node (ref "PhT-7") (pin "4") (pinfunction "C_4") (pintype "passive"))
    )
    (net (code "76") (name "Net-(LED8-K)") (class "Default")
      (node (ref "LED8") (pin "2") (pinfunction "K_2") (pintype "passive"))
      (node (ref "PhT-8") (pin "4") (pinfunction "C_4") (pintype "passive"))
    )
    (net (code "77") (name "Net-(PhT-1-K)") (class "Default")
      (node (ref "PhT-1") (pin "2") (pinfunction "K_2") (pintype "passive"))
      (node (ref "R1") (pin "2") (pinfunction "2_2") (pintype "passive"))
    )
    (net (code "78") (name "Net-(PhT-2-K)") (class "Default")
      (node (ref "PhT-2") (pin "2") (pinfunction "K_2") (pintype "passive"))
      (node (ref "R2") (pin "2") (pinfunction "2_2") (pintype "passive"))
    )
    (net (code "79") (name "Net-(PhT-3-K)") (class "Default")
      (node (ref "PhT-3") (pin "2") (pinfunction "K_2") (pintype "passive"))
      (node (ref "R3") (pin "2") (pinfunction "2_2") (pintype "passive"))
    )
    (net (code "80") (name "Net-(PhT-4-K)") (class "Default")
      (node (ref "PhT-4") (pin "2") (pinfunction "K_2") (pintype "passive"))
      (node (ref "R4") (pin "2") (pinfunction "2_2") (pintype "passive"))
    )
    (net (code "81") (name "Net-(PhT-5-K)") (class "Default")
      (node (ref "PhT-5") (pin "2") (pinfunction "K_2") (pintype "passive"))
      (node (ref "R5") (pin "2") (pinfunction "2_2") (pintype "passive"))
    )
    (net (code "82") (name "Net-(PhT-6-K)") (class "Default")
      (node (ref "PhT-6") (pin "2") (pinfunction "K_2") (pintype "passive"))
      (node (ref "R6") (pin "2") (pinfunction "2_2") (pintype "passive"))
    )
    (net (code "83") (name "Net-(PhT-7-K)") (class "Default")
      (node (ref "PhT-7") (pin "2") (pinfunction "K_2") (pintype "passive"))
      (node (ref "R7") (pin "2") (pinfunction "2_2") (pintype "passive"))
    )
    (net (code "84") (name "Net-(PhT-8-K)") (class "Default")
      (node (ref "PhT-8") (pin "2") (pinfunction "K_2") (pintype "passive"))
      (node (ref "R8") (pin "2") (pinfunction "2_2") (pintype "passive"))
    )
    (net (code "85") (name "V+") (class "Default")
      (node (ref "D1") (pin "2") (pinfunction "K_2") (pintype "passive"))
      (node (ref "D10") (pin "2") (pinfunction "K_2") (pintype "passive"))
      (node (ref "D2") (pin "2") (pinfunction "K_2") (pintype "passive"))
      (node (ref "D3") (pin "2") (pinfunction "K_2") (pintype "passive"))
      (node (ref "D4") (pin "2") (pinfunction "K_2") (pintype "passive"))
      (node (ref "D5") (pin "2") (pinfunction "K_2") (pintype "passive"))
      (node (ref "D6") (pin "2") (pinfunction "K_2") (pintype "passive"))
      (node (ref "D7") (pin "2") (pinfunction "K_2") (pintype "passive"))
      (node (ref "D8") (pin "2") (pinfunction "K_2") (pintype "passive"))
      (node (ref "D9") (pin "2") (pinfunction "K_2") (pintype "passive"))
      (node (ref "RL1") (pin "A2") (pinfunction "A2_A2") (pintype "passive"))
      (node (ref "RL2") (pin "A2") (pinfunction "A2_A2") (pintype "passive"))
      (node (ref "RL3") (pin "A2") (pinfunction "A2_A2") (pintype "passive"))
      (node (ref "RL4") (pin "A2") (pinfunction "A2_A2") (pintype "passive"))
      (node (ref "RL5") (pin "A2") (pinfunction "A2_A2") (pintype "passive"))
      (node (ref "RL6") (pin "A2") (pinfunction "A2_A2") (pintype "passive"))
      (node (ref "RL7") (pin "A2") (pinfunction "A2_A2") (pintype "passive"))
      (node (ref "RL8") (pin "A2") (pinfunction "A2_A2") (pintype "passive"))
    )
    (net (code "86") (name "VCC") (class "Default")
      (node (ref "C3") (pin "2") (pinfunction "-_2") (pintype "passive"))
      (node (ref "C4") (pin "2") (pinfunction "P_2") (pintype "passive"))
      (node (ref "C5") (pin "2") (pinfunction "-_2") (pintype "passive"))
      (node (ref "D11") (pin "2") (pinfunction "K_2") (pintype "passive"))
      (node (ref "U1") (pin "20") (pinfunction "VCC_20") (pintype "power_in"))
    )
    (net (code "87") (name "unconnected-(OUT-Pad17)") (class "Default")
      (node (ref "OUT") (pin "17") (pinfunction "17_17") (pintype "passive"))
    )
  )
)
